# SCH_Hu-Tao-PCB-Card-_fixed-ver__2024-07-.net
KiCad netlist of a schematic drawn in EasyEDA
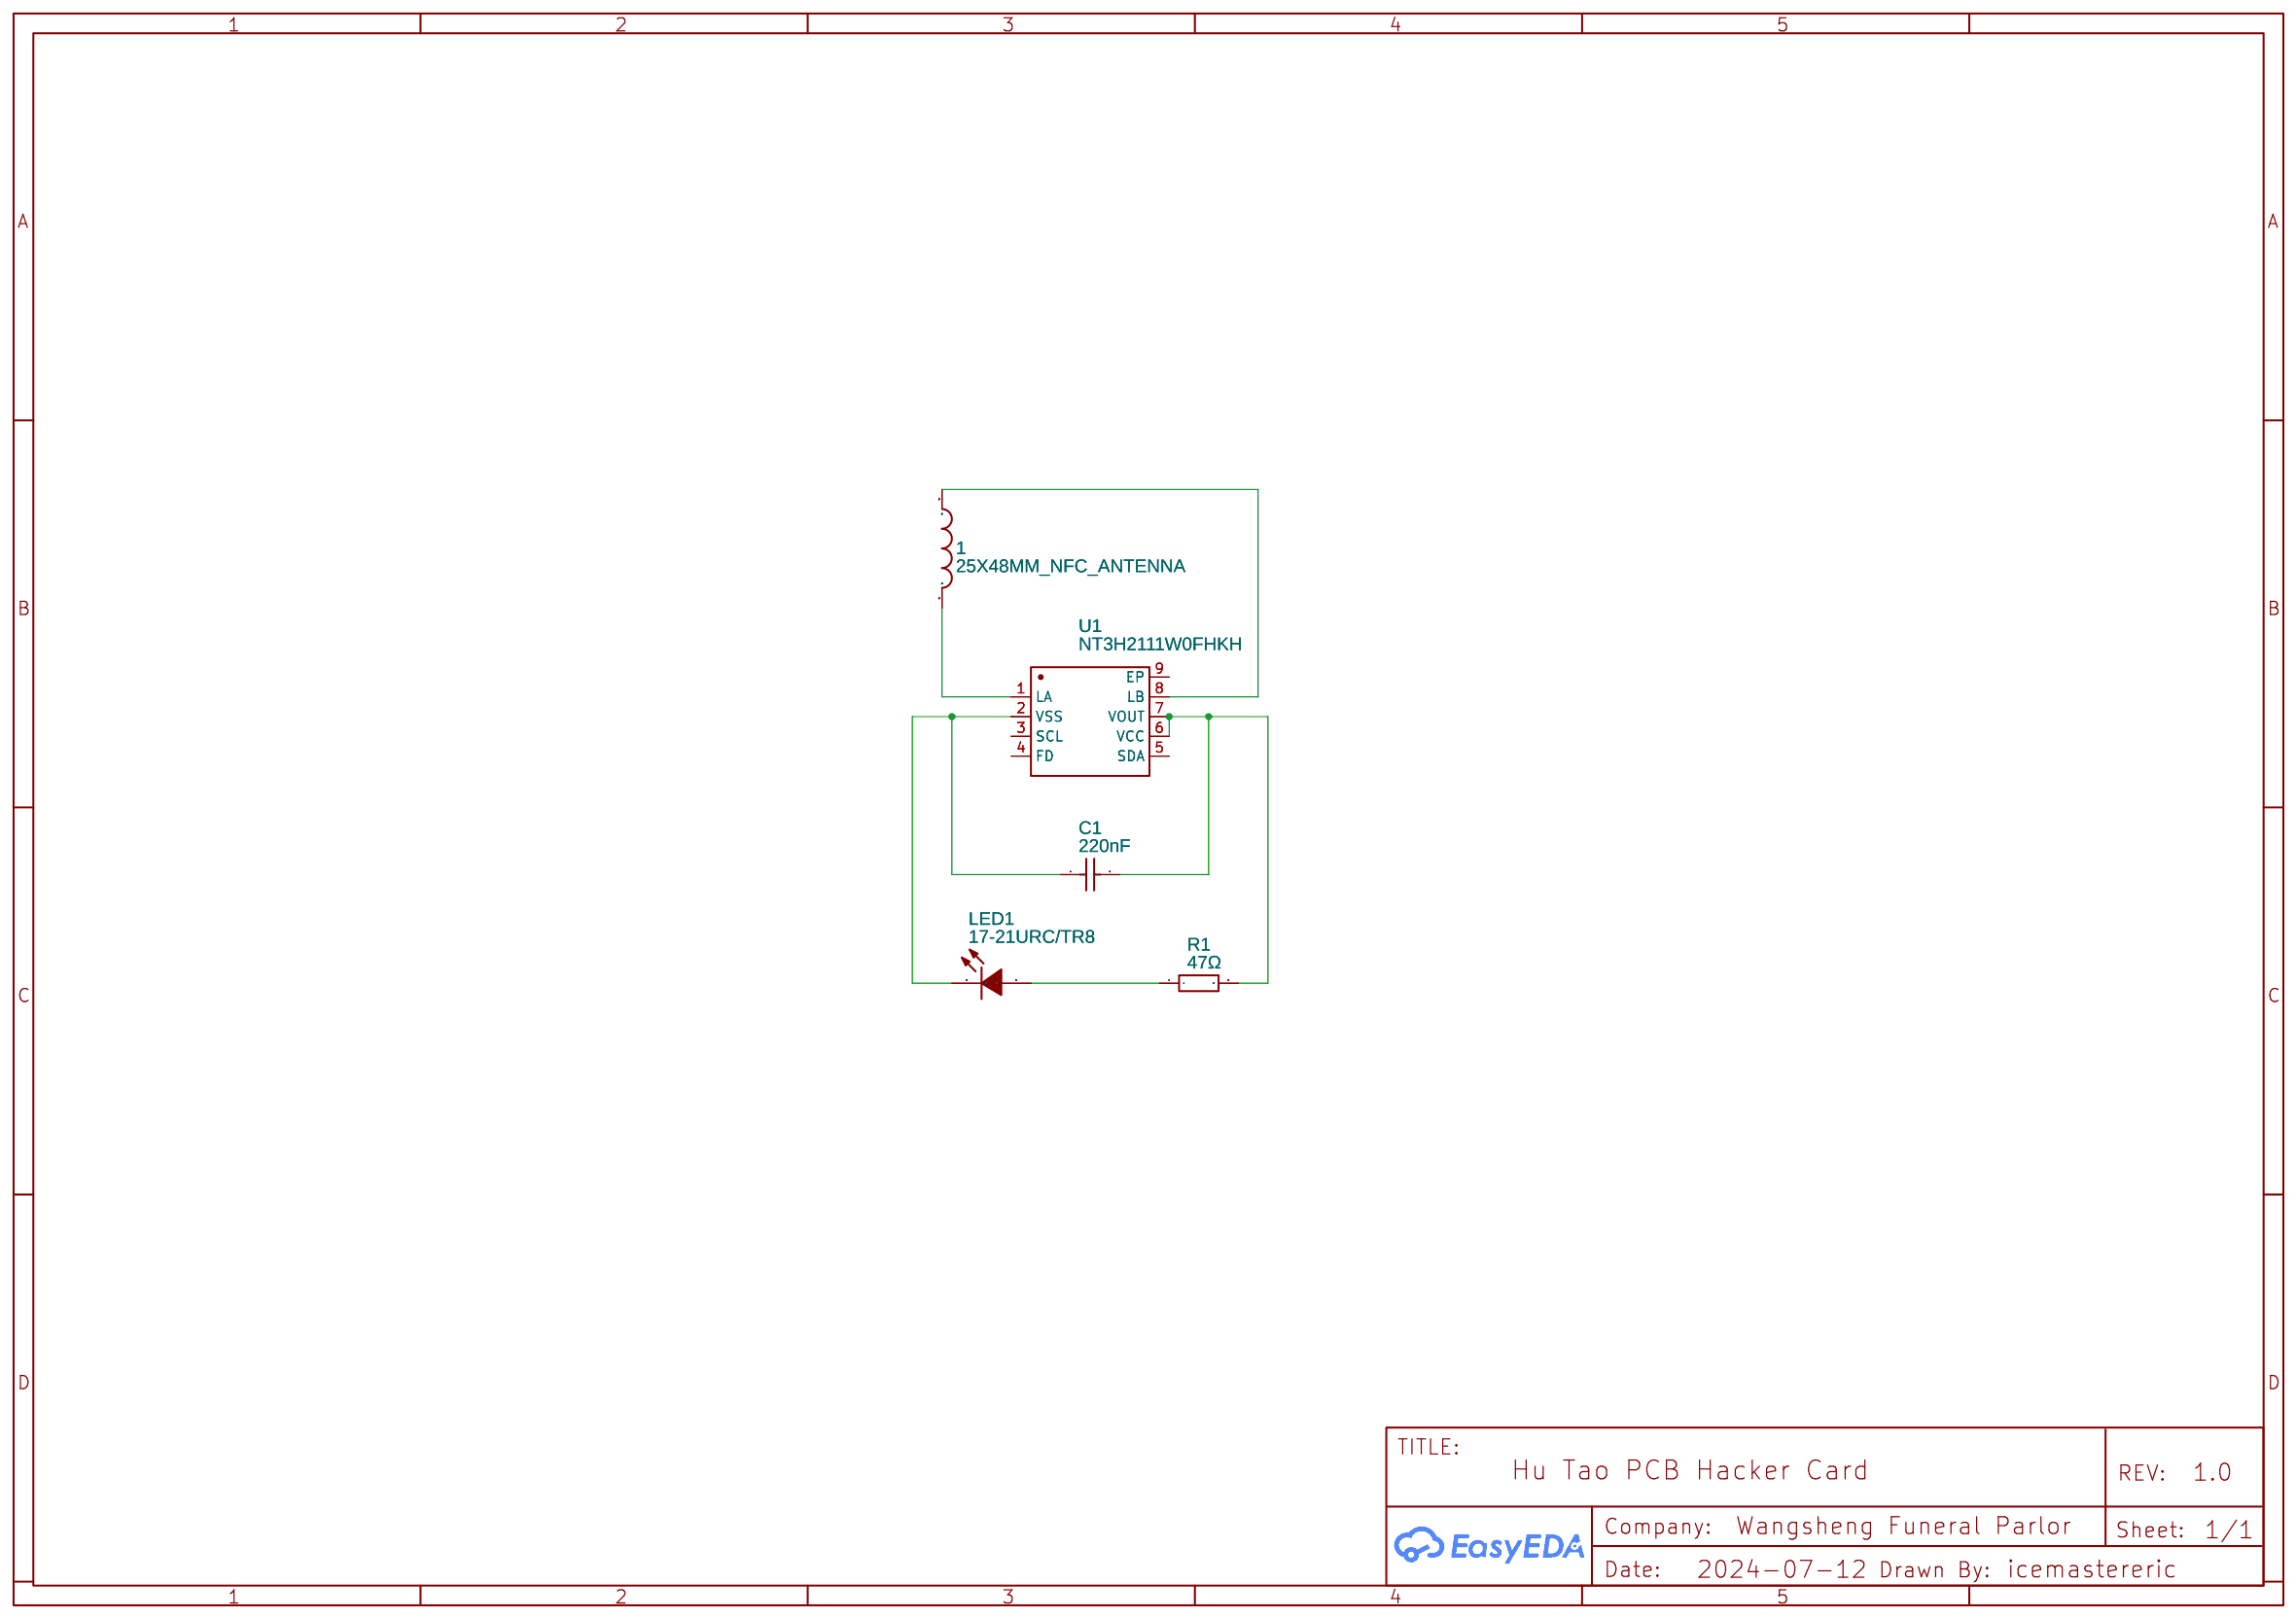
[diagram p0: schematic sheet]

(export (version "E")
  (design (tool "Eeschema 10.0.6"))
  (components
    (comp (ref "1") (value "25X48MM_NFC_ANTENNA") (libsource (lib "") (part "25X48MM_NFC_ANTENNA")))
    (comp (ref "C1")
      (value "220nF")
      (fields
        (field (name "Manufacturer Part") "CL10B224KA8NNNC")
        (field (name "Manufacturer") "SAMSUNG(三星)")
      )
      (libsource (lib "") (part "CL10B224KA8NNNC"))
    )
    (comp (ref "LED1")
      (value "17-21URC/TR8")
      (fields (field (name "Manufacturer") "EVERLIGHT(亿光)"))
      (libsource (lib "") (part "17-21URC/TR8"))
    )
    (comp (ref "R1")
      (value "47Ω")
      (fields
        (field (name "Manufacturer Part") "0603WAF470JT5E")
        (field (name "Manufacturer") "UNI-ROYAL(厚声)")
      )
      (libsource (lib "") (part "0603WAF470JT5E"))
    )
    (comp (ref "U1")
      (value "NT3H2111W0FHKH")
      (fields (field (name "Manufacturer") "NXP(恩智浦)"))
      (libsource (lib "") (part "NT3H2111W0FHKH"))
    )
  )
  (nets
    (net (code "1") (name "Net-(LED1-A)") (class "Default")
      (node (ref "LED1") (pin "1") (pinfunction "A_1") (pintype "unspecified"))
      (node (ref "R1") (pin "1") (pinfunction "1_1") (pintype "input"))
    )
    (net (code "2") (name "Net-(LED1-K)") (class "Default")
      (node (ref "C1") (pin "1") (pinfunction "1_1") (pintype "input"))
      (node (ref "LED1") (pin "2") (pinfunction "K_2") (pintype "unspecified"))
      (node (ref "U1") (pin "2") (pinfunction "VSS_2") (pintype "unspecified"))
    )
    (net (code "3") (name "Net-(U1-LA)") (class "Default")
      (node (ref "1") (pin "P$2") (pinfunction "P$2_P$2") (pintype "bidirectional"))
      (node (ref "U1") (pin "1") (pinfunction "LA_1") (pintype "unspecified"))
    )
    (net (code "4") (name "Net-(U1-LB)") (class "Default")
      (node (ref "1") (pin "P$1") (pinfunction "P$1_P$1") (pintype "bidirectional"))
      (node (ref "U1") (pin "8") (pinfunction "LB_8") (pintype "unspecified"))
    )
    (net (code "5") (name "Net-(U1-VCC)") (class "Default")
      (node (ref "C1") (pin "2") (pinfunction "2_2") (pintype "input"))
      (node (ref "R1") (pin "2") (pinfunction "2_2") (pintype "input"))
      (node (ref "U1") (pin "6") (pinfunction "VCC_6") (pintype "unspecified"))
      (node (ref "U1") (pin "7") (pinfunction "VOUT_7") (pintype "unspecified"))
    )
    (net (code "6") (name "unconnected-(U1-EP-Pad9)") (class "Default")
      (node (ref "U1") (pin "9") (pinfunction "EP_9") (pintype "unspecified"))
    )
    (net (code "7") (name "unconnected-(U1-FD-Pad4)") (class "Default")
      (node (ref "U1") (pin "4") (pinfunction "FD_4") (pintype "unspecified"))
    )
    (net (code "8") (name "unconnected-(U1-SCL-Pad3)") (class "Default")
      (node (ref "U1") (pin "3") (pinfunction "SCL_3") (pintype "unspecified"))
    )
    (net (code "9") (name "unconnected-(U1-SDA-Pad5)") (class "Default")
      (node (ref "U1") (pin "5") (pinfunction "SDA_5") (pintype "unspecified"))
    )
  )
)
